# fancontrollermegashield.net
KiCad netlist of a schematic drawn in EAGLE
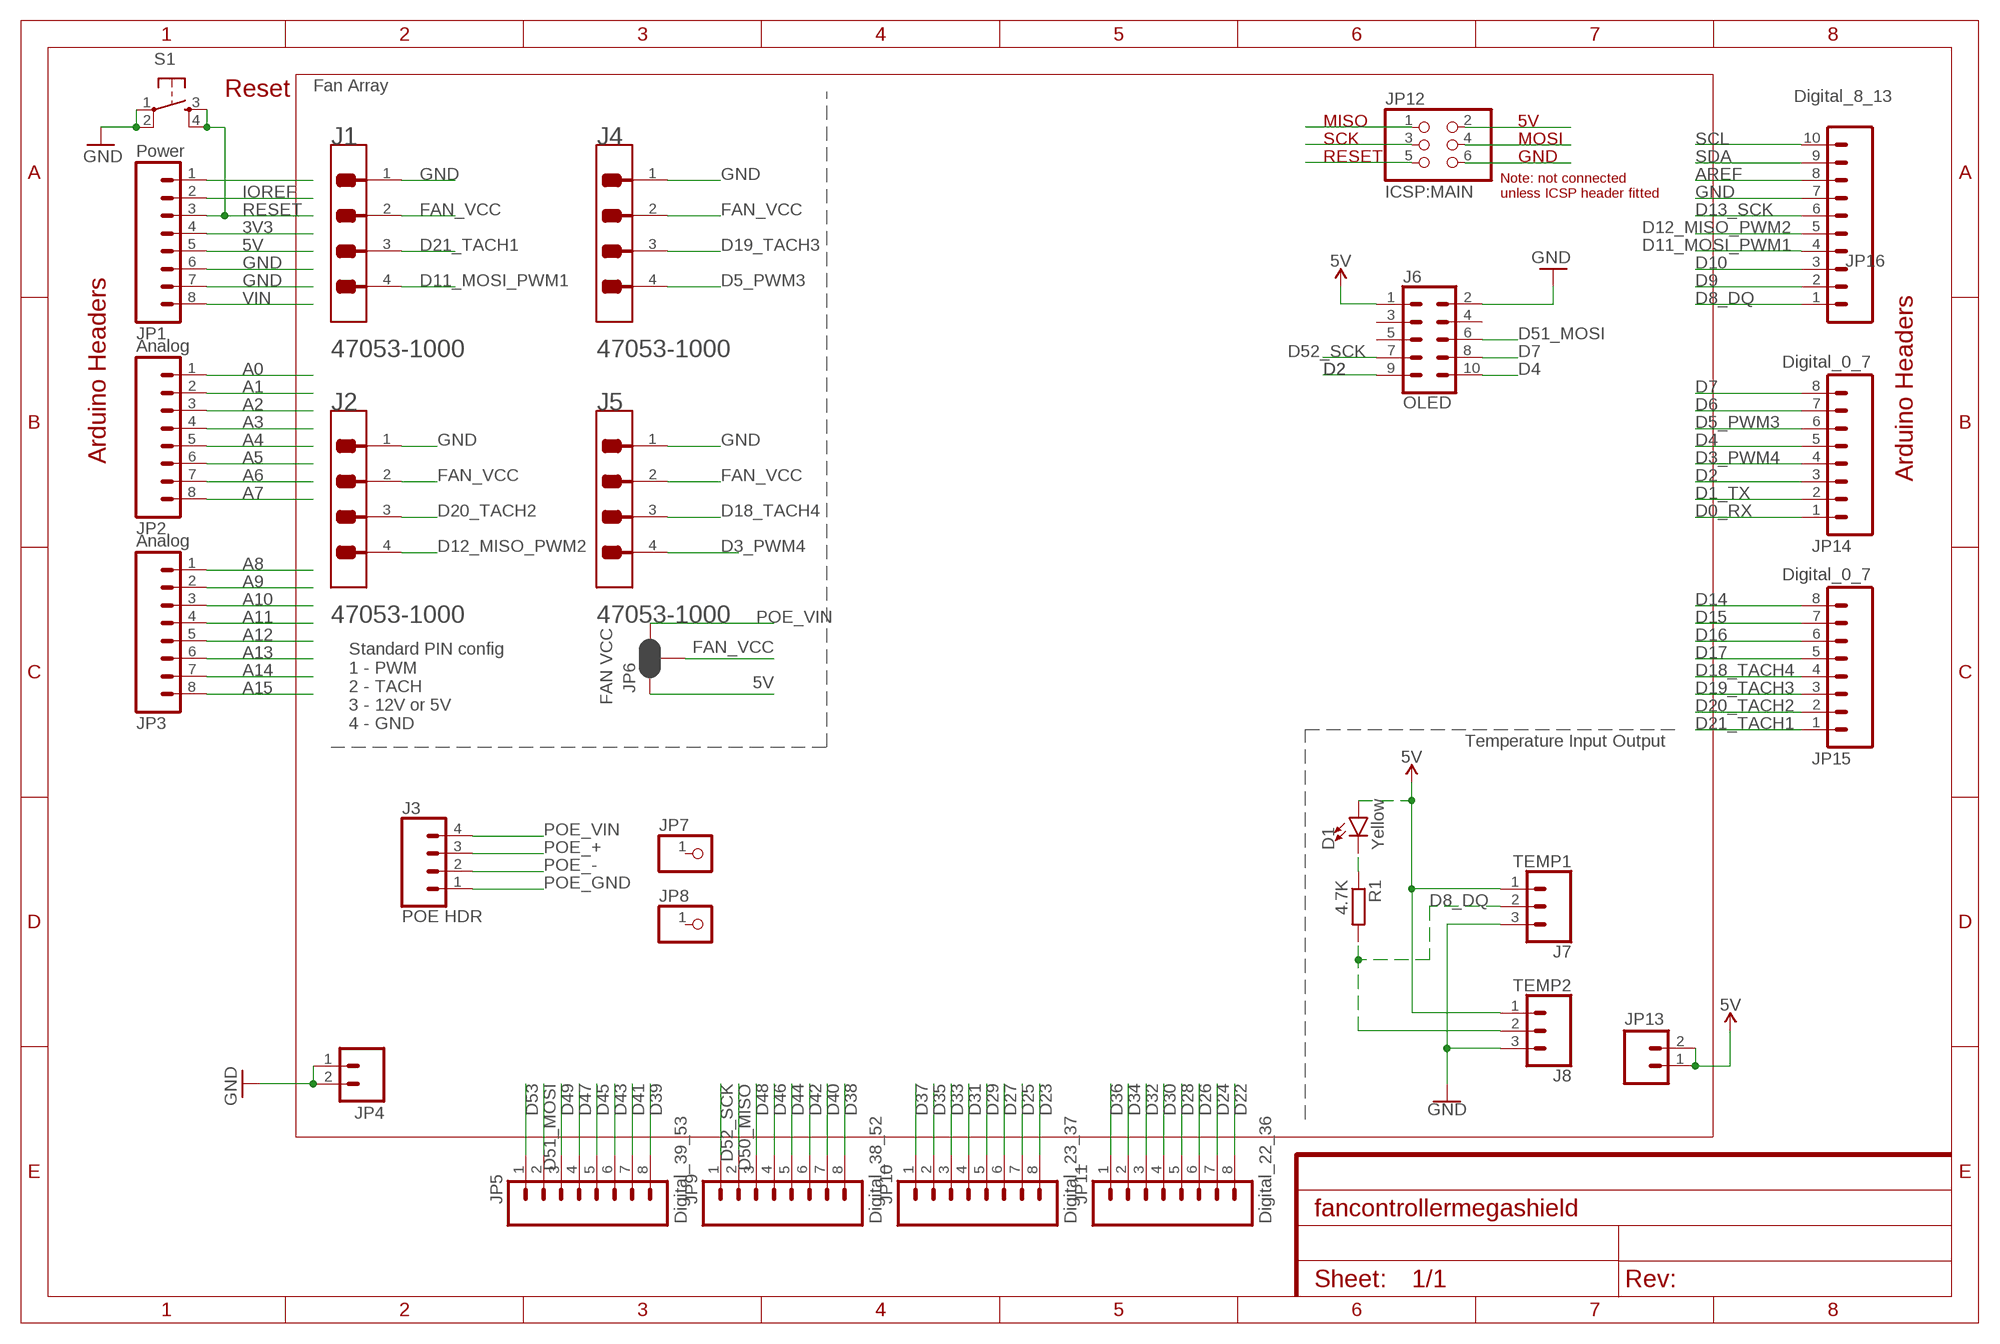
[diagram p0: schematic, sheet 1]

(export (version "E")
  (design (tool "Eeschema 10.0.6"))
  (components
    (comp (ref "D1")
      (value "Yellow")
      (footprint "eagle-import:LED-0603")
      (libsource (lib "eagle-import") (part "LED-YELLOW0603"))
    )
    (comp (ref "J1")
      (value "FAN1")
      (footprint "eagle-import:MOLEX_47053-1000_0")
      (fields
        (field (name "DIGIKEY_PART_NUMBER") "WM4330-ND")
        (field (name "MF") "Molex")
        (field (name "MOUSER_PART_NUMBER") "538-47053-1000")
      )
      (libsource (lib "eagle-import") (part "MOLEX_47053-1000MOLEX_47053-1000_0_0"))
    )
    (comp (ref "J2")
      (value "MOLEX_47053-1000MOLEX_47053-1000_0_0")
      (footprint "eagle-import:MOLEX_47053-1000_0")
      (fields
        (field (name "DIGIKEY_PART_NUMBER") "WM4330-ND")
        (field (name "MF") "Molex")
        (field (name "MOUSER_PART_NUMBER") "538-47053-1000")
      )
      (libsource (lib "eagle-import") (part "MOLEX_47053-1000MOLEX_47053-1000_0_0"))
    )
    (comp (ref "J3")
      (value "POE HDR")
      (footprint "eagle-import:1X04")
      (libsource (lib "eagle-import") (part "CONN_04"))
    )
    (comp (ref "J4")
      (value "MOLEX_47053-1000MOLEX_47053-1000_0_0")
      (footprint "eagle-import:MOLEX_47053-1000_0")
      (fields
        (field (name "DIGIKEY_PART_NUMBER") "WM4330-ND")
        (field (name "MF") "Molex")
        (field (name "MOUSER_PART_NUMBER") "538-47053-1000")
      )
      (libsource (lib "eagle-import") (part "MOLEX_47053-1000MOLEX_47053-1000_0_0"))
    )
    (comp (ref "J5")
      (value "MOLEX_47053-1000MOLEX_47053-1000_0_0")
      (footprint "eagle-import:MOLEX_47053-1000_0")
      (fields
        (field (name "DIGIKEY_PART_NUMBER") "WM4330-ND")
        (field (name "MF") "Molex")
        (field (name "MOUSER_PART_NUMBER") "538-47053-1000")
      )
      (libsource (lib "eagle-import") (part "MOLEX_47053-1000MOLEX_47053-1000_0_0"))
    )
    (comp (ref "J6")
      (value "OLED")
      (footprint "eagle-import:2X5-SHROUDED")
      (libsource (lib "eagle-import") (part "CONN_05X2SHD"))
    )
    (comp (ref "J7")
      (value "TEMP1")
      (footprint "eagle-import:MOLEX-1X3")
      (libsource (lib "eagle-import") (part "CONN_03POLAR"))
    )
    (comp (ref "J8")
      (value "TEMP2")
      (footprint "eagle-import:MOLEX-1X3")
      (libsource (lib "eagle-import") (part "CONN_03POLAR"))
    )
    (comp (ref "JP1")
      (value "Power")
      (footprint "eagle-import:1X08")
      (libsource (lib "eagle-import") (part "freetronics-master-v1_M08"))
    )
    (comp (ref "JP2")
      (value "Analog")
      (footprint "eagle-import:1X08")
      (libsource (lib "eagle-import") (part "freetronics-master-v1_M08"))
    )
    (comp (ref "JP3")
      (value "Analog")
      (footprint "eagle-import:1X08")
      (libsource (lib "eagle-import") (part "freetronics-master-v1_M08"))
    )
    (comp (ref "JP4")
      (value "M02PTH")
      (footprint "eagle-import:1X02")
      (libsource (lib "eagle-import") (part "M02PTH"))
    )
    (comp (ref "JP5")
      (value "Digital_39_53")
      (footprint "eagle-import:1X08")
      (libsource (lib "eagle-import") (part "M08"))
    )
    (comp (ref "JP6")
      (value "FAN VCC")
      (footprint "eagle-import:SMT-JUMPER_3_2-NC_PASTE_SILK")
      (libsource (lib "eagle-import") (part "JUMPER-SMT_3_2-NC_PASTE_SILK"))
    )
    (comp (ref "JP7")
      (value "PINHD-1X1")
      (footprint "eagle-import:1X01")
      (libsource (lib "eagle-import") (part "PINHD-1X1"))
    )
    (comp (ref "JP8")
      (value "PINHD-1X1")
      (footprint "eagle-import:1X01")
      (libsource (lib "eagle-import") (part "PINHD-1X1"))
    )
    (comp (ref "JP9")
      (value "Digital_38_52")
      (footprint "eagle-import:1X08")
      (libsource (lib "eagle-import") (part "M08"))
    )
    (comp (ref "JP10")
      (value "Digital_23_37")
      (footprint "eagle-import:1X08")
      (libsource (lib "eagle-import") (part "M08"))
    )
    (comp (ref "JP11")
      (value "Digital_22_36")
      (footprint "eagle-import:1X08")
      (libsource (lib "eagle-import") (part "M08"))
    )
    (comp (ref "JP12")
      (value "ICSP:MAIN")
      (footprint "eagle-import:2X03")
      (libsource (lib "eagle-import") (part "PINHD-2X3"))
    )
    (comp (ref "JP13")
      (value "M02PTH")
      (footprint "eagle-import:1X02")
      (libsource (lib "eagle-import") (part "M02PTH"))
    )
    (comp (ref "JP14")
      (value "Digital_0_7")
      (footprint "eagle-import:1X08")
      (libsource (lib "eagle-import") (part "M08"))
    )
    (comp (ref "JP15")
      (value "Digital_0_7")
      (footprint "eagle-import:1X08")
      (libsource (lib "eagle-import") (part "M08"))
    )
    (comp (ref "JP16")
      (value "Digital_8_13")
      (footprint "eagle-import:1X10")
      (libsource (lib "eagle-import") (part "M100.1"))
    )
    (comp (ref "R1")
      (value "4.7K")
      (footprint "eagle-import:R0603")
      (libsource (lib "eagle-import") (part "R-EU_R0603"))
    )
    (comp (ref "S1")
      (value "TAC_SWITCHPTH")
      (footprint "eagle-import:TACTILE-PTH")
      (libsource (lib "eagle-import") (part "TAC_SWITCHPTH"))
    )
  )
  (nets
    (net (code "1") (name "/3V3") (class "Default")
      (node (ref "JP1") (pin "4") (pinfunction "4_4") (pintype "passive"))
    )
    (net (code "2") (name "/A0") (class "Default")
      (node (ref "JP2") (pin "1") (pinfunction "1_1") (pintype "passive"))
    )
    (net (code "3") (name "/A1") (class "Default")
      (node (ref "JP2") (pin "2") (pinfunction "2_2") (pintype "passive"))
    )
    (net (code "4") (name "/A2") (class "Default")
      (node (ref "JP2") (pin "3") (pinfunction "3_3") (pintype "passive"))
    )
    (net (code "5") (name "/A3") (class "Default")
      (node (ref "JP2") (pin "4") (pinfunction "4_4") (pintype "passive"))
    )
    (net (code "6") (name "/A4") (class "Default")
      (node (ref "JP2") (pin "5") (pinfunction "5_5") (pintype "passive"))
    )
    (net (code "7") (name "/A5") (class "Default")
      (node (ref "JP2") (pin "6") (pinfunction "6_6") (pintype "passive"))
    )
    (net (code "8") (name "/A6") (class "Default")
      (node (ref "JP2") (pin "7") (pinfunction "7_7") (pintype "passive"))
    )
    (net (code "9") (name "/A7") (class "Default")
      (node (ref "JP2") (pin "8") (pinfunction "8_8") (pintype "passive"))
    )
    (net (code "10") (name "/A8") (class "Default")
      (node (ref "JP3") (pin "1") (pinfunction "1_1") (pintype "passive"))
    )
    (net (code "11") (name "/A9") (class "Default")
      (node (ref "JP3") (pin "2") (pinfunction "2_2") (pintype "passive"))
    )
    (net (code "12") (name "/A10") (class "Default")
      (node (ref "JP3") (pin "3") (pinfunction "3_3") (pintype "passive"))
    )
    (net (code "13") (name "/A11") (class "Default")
      (node (ref "JP3") (pin "4") (pinfunction "4_4") (pintype "passive"))
    )
    (net (code "14") (name "/A12") (class "Default")
      (node (ref "JP3") (pin "5") (pinfunction "5_5") (pintype "passive"))
    )
    (net (code "15") (name "/A13") (class "Default")
      (node (ref "JP3") (pin "6") (pinfunction "6_6") (pintype "passive"))
    )
    (net (code "16") (name "/A14") (class "Default")
      (node (ref "JP3") (pin "7") (pinfunction "7_7") (pintype "passive"))
    )
    (net (code "17") (name "/A15") (class "Default")
      (node (ref "JP3") (pin "8") (pinfunction "8_8") (pintype "passive"))
    )
    (net (code "18") (name "/AREF") (class "Default")
      (node (ref "JP16") (pin "8") (pinfunction "8_8") (pintype "passive"))
    )
    (net (code "19") (name "/D0_RX") (class "Default")
      (node (ref "JP14") (pin "1") (pinfunction "1_1") (pintype "passive"))
    )
    (net (code "20") (name "/D1_TX") (class "Default")
      (node (ref "JP14") (pin "2") (pinfunction "2_2") (pintype "passive"))
    )
    (net (code "21") (name "/D2") (class "Default")
      (node (ref "J6") (pin "9") (pinfunction "9_9") (pintype "passive"))
      (node (ref "JP14") (pin "3") (pinfunction "3_3") (pintype "passive"))
    )
    (net (code "22") (name "/D3_PWM4") (class "Default")
      (node (ref "J5") (pin "4") (pinfunction "4_4") (pintype "bidirectional"))
      (node (ref "JP14") (pin "4") (pinfunction "4_4") (pintype "passive"))
    )
    (net (code "23") (name "/D4") (class "Default")
      (node (ref "J6") (pin "10") (pinfunction "10_10") (pintype "passive"))
      (node (ref "JP14") (pin "5") (pinfunction "5_5") (pintype "passive"))
    )
    (net (code "24") (name "/D5_PWM3") (class "Default")
      (node (ref "J4") (pin "4") (pinfunction "4_4") (pintype "bidirectional"))
      (node (ref "JP14") (pin "6") (pinfunction "6_6") (pintype "passive"))
    )
    (net (code "25") (name "/D6") (class "Default")
      (node (ref "JP14") (pin "7") (pinfunction "7_7") (pintype "passive"))
    )
    (net (code "26") (name "/D7") (class "Default")
      (node (ref "J6") (pin "8") (pinfunction "8_8") (pintype "passive"))
      (node (ref "JP14") (pin "8") (pinfunction "8_8") (pintype "passive"))
    )
    (net (code "27") (name "/D8_DQ") (class "Default")
      (node (ref "J7") (pin "2") (pinfunction "2_2") (pintype "passive"))
      (node (ref "J8") (pin "2") (pinfunction "2_2") (pintype "passive"))
      (node (ref "JP16") (pin "1") (pinfunction "1_1") (pintype "passive"))
      (node (ref "R1") (pin "2") (pinfunction "2_2") (pintype "passive"))
    )
    (net (code "28") (name "/D9") (class "Default")
      (node (ref "JP16") (pin "2") (pinfunction "2_2") (pintype "passive"))
    )
    (net (code "29") (name "/D10") (class "Default")
      (node (ref "JP16") (pin "3") (pinfunction "3_3") (pintype "passive"))
    )
    (net (code "30") (name "/D11_MOSI_PWM1") (class "Default")
      (node (ref "J1") (pin "4") (pinfunction "4_4") (pintype "bidirectional"))
      (node (ref "JP16") (pin "4") (pinfunction "4_4") (pintype "passive"))
    )
    (net (code "31") (name "/D12_MISO_PWM2") (class "Default")
      (node (ref "J2") (pin "4") (pinfunction "4_4") (pintype "bidirectional"))
      (node (ref "JP16") (pin "5") (pinfunction "5_5") (pintype "passive"))
    )
    (net (code "32") (name "/D13_SCK") (class "Default")
      (node (ref "JP16") (pin "6") (pinfunction "6_6") (pintype "passive"))
    )
    (net (code "33") (name "/D14") (class "Default")
      (node (ref "JP15") (pin "8") (pinfunction "8_8") (pintype "passive"))
    )
    (net (code "34") (name "/D15") (class "Default")
      (node (ref "JP15") (pin "7") (pinfunction "7_7") (pintype "passive"))
    )
    (net (code "35") (name "/D16") (class "Default")
      (node (ref "JP15") (pin "6") (pinfunction "6_6") (pintype "passive"))
    )
    (net (code "36") (name "/D17") (class "Default")
      (node (ref "JP15") (pin "5") (pinfunction "5_5") (pintype "passive"))
    )
    (net (code "37") (name "/D18_TACH4") (class "Default")
      (node (ref "J5") (pin "3") (pinfunction "3_3") (pintype "bidirectional"))
      (node (ref "JP15") (pin "4") (pinfunction "4_4") (pintype "passive"))
    )
    (net (code "38") (name "/D19_TACH3") (class "Default")
      (node (ref "J4") (pin "3") (pinfunction "3_3") (pintype "bidirectional"))
      (node (ref "JP15") (pin "3") (pinfunction "3_3") (pintype "passive"))
    )
    (net (code "39") (name "/D20_TACH2") (class "Default")
      (node (ref "J2") (pin "3") (pinfunction "3_3") (pintype "bidirectional"))
      (node (ref "JP15") (pin "2") (pinfunction "2_2") (pintype "passive"))
    )
    (net (code "40") (name "/D21_TACH1") (class "Default")
      (node (ref "J1") (pin "3") (pinfunction "3_3") (pintype "bidirectional"))
      (node (ref "JP15") (pin "1") (pinfunction "1_1") (pintype "passive"))
    )
    (net (code "41") (name "/D22") (class "Default")
      (node (ref "JP11") (pin "8") (pinfunction "8_8") (pintype "passive"))
    )
    (net (code "42") (name "/D23") (class "Default")
      (node (ref "JP10") (pin "8") (pinfunction "8_8") (pintype "passive"))
    )
    (net (code "43") (name "/D24") (class "Default")
      (node (ref "JP11") (pin "7") (pinfunction "7_7") (pintype "passive"))
    )
    (net (code "44") (name "/D25") (class "Default")
      (node (ref "JP10") (pin "7") (pinfunction "7_7") (pintype "passive"))
    )
    (net (code "45") (name "/D26") (class "Default")
      (node (ref "JP11") (pin "6") (pinfunction "6_6") (pintype "passive"))
    )
    (net (code "46") (name "/D27") (class "Default")
      (node (ref "JP10") (pin "6") (pinfunction "6_6") (pintype "passive"))
    )
    (net (code "47") (name "/D28") (class "Default")
      (node (ref "JP11") (pin "5") (pinfunction "5_5") (pintype "passive"))
    )
    (net (code "48") (name "/D29") (class "Default")
      (node (ref "JP10") (pin "5") (pinfunction "5_5") (pintype "passive"))
    )
    (net (code "49") (name "/D30") (class "Default")
      (node (ref "JP11") (pin "4") (pinfunction "4_4") (pintype "passive"))
    )
    (net (code "50") (name "/D31") (class "Default")
      (node (ref "JP10") (pin "4") (pinfunction "4_4") (pintype "passive"))
    )
    (net (code "51") (name "/D32") (class "Default")
      (node (ref "JP11") (pin "3") (pinfunction "3_3") (pintype "passive"))
    )
    (net (code "52") (name "/D33") (class "Default")
      (node (ref "JP10") (pin "3") (pinfunction "3_3") (pintype "passive"))
    )
    (net (code "53") (name "/D34") (class "Default")
      (node (ref "JP11") (pin "2") (pinfunction "2_2") (pintype "passive"))
    )
    (net (code "54") (name "/D35") (class "Default")
      (node (ref "JP10") (pin "2") (pinfunction "2_2") (pintype "passive"))
    )
    (net (code "55") (name "/D36") (class "Default")
      (node (ref "JP11") (pin "1") (pinfunction "1_1") (pintype "passive"))
    )
    (net (code "56") (name "/D37") (class "Default")
      (node (ref "JP10") (pin "1") (pinfunction "1_1") (pintype "passive"))
    )
    (net (code "57") (name "/D38") (class "Default")
      (node (ref "JP9") (pin "8") (pinfunction "8_8") (pintype "passive"))
    )
    (net (code "58") (name "/D39") (class "Default")
      (node (ref "JP5") (pin "8") (pinfunction "8_8") (pintype "passive"))
    )
    (net (code "59") (name "/D40") (class "Default")
      (node (ref "JP9") (pin "7") (pinfunction "7_7") (pintype "passive"))
    )
    (net (code "60") (name "/D41") (class "Default")
      (node (ref "JP5") (pin "7") (pinfunction "7_7") (pintype "passive"))
    )
    (net (code "61") (name "/D42") (class "Default")
      (node (ref "JP9") (pin "6") (pinfunction "6_6") (pintype "passive"))
    )
    (net (code "62") (name "/D43") (class "Default")
      (node (ref "JP5") (pin "6") (pinfunction "6_6") (pintype "passive"))
    )
    (net (code "63") (name "/D44") (class "Default")
      (node (ref "JP9") (pin "5") (pinfunction "5_5") (pintype "passive"))
    )
    (net (code "64") (name "/D45") (class "Default")
      (node (ref "JP5") (pin "5") (pinfunction "5_5") (pintype "passive"))
    )
    (net (code "65") (name "/D46") (class "Default")
      (node (ref "JP9") (pin "4") (pinfunction "4_4") (pintype "passive"))
    )
    (net (code "66") (name "/D47") (class "Default")
      (node (ref "JP5") (pin "4") (pinfunction "4_4") (pintype "passive"))
    )
    (net (code "67") (name "/D48") (class "Default")
      (node (ref "JP9") (pin "3") (pinfunction "3_3") (pintype "passive"))
    )
    (net (code "68") (name "/D49") (class "Default")
      (node (ref "JP5") (pin "3") (pinfunction "3_3") (pintype "passive"))
    )
    (net (code "69") (name "/D50_MISO") (class "Default")
      (node (ref "JP9") (pin "2") (pinfunction "2_2") (pintype "passive"))
    )
    (net (code "70") (name "/D51_MOSI") (class "Default")
      (node (ref "J6") (pin "6") (pinfunction "6_6") (pintype "passive"))
      (node (ref "JP5") (pin "2") (pinfunction "2_2") (pintype "passive"))
    )
    (net (code "71") (name "/D52_SCK") (class "Default")
      (node (ref "J6") (pin "7") (pinfunction "7_7") (pintype "passive"))
      (node (ref "JP9") (pin "1") (pinfunction "1_1") (pintype "passive"))
    )
    (net (code "72") (name "/D53") (class "Default")
      (node (ref "JP5") (pin "1") (pinfunction "1_1") (pintype "passive"))
    )
    (net (code "73") (name "/FAN_VCC") (class "Default")
      (node (ref "J1") (pin "2") (pinfunction "2_2") (pintype "bidirectional"))
      (node (ref "J2") (pin "2") (pinfunction "2_2") (pintype "bidirectional"))
      (node (ref "J4") (pin "2") (pinfunction "2_2") (pintype "bidirectional"))
      (node (ref "J5") (pin "2") (pinfunction "2_2") (pintype "bidirectional"))
      (node (ref "JP6") (pin "2") (pinfunction "2_2") (pintype "passive"))
    )
    (net (code "74") (name "/IOREF") (class "Default")
      (node (ref "JP1") (pin "2") (pinfunction "2_2") (pintype "passive"))
    )
    (net (code "75") (name "/POE_+") (class "Default")
      (node (ref "J3") (pin "3") (pinfunction "3_3") (pintype "passive"))
    )
    (net (code "76") (name "/POE_-") (class "Default")
      (node (ref "J3") (pin "2") (pinfunction "2_2") (pintype "passive"))
    )
    (net (code "77") (name "/POE_GND") (class "Default")
      (node (ref "J3") (pin "1") (pinfunction "1_1") (pintype "passive"))
    )
    (net (code "78") (name "/POE_VIN") (class "Default")
      (node (ref "J3") (pin "4") (pinfunction "4_4") (pintype "passive"))
      (node (ref "JP6") (pin "3") (pinfunction "3_3") (pintype "passive"))
    )
    (net (code "79") (name "/RESET") (class "Default")
      (node (ref "JP1") (pin "3") (pinfunction "3_3") (pintype "passive"))
      (node (ref "S1") (pin "3") (pinfunction "3_3") (pintype "passive"))
      (node (ref "S1") (pin "4") (pinfunction "4_4") (pintype "passive"))
    )
    (net (code "80") (name "/SCL") (class "Default")
      (node (ref "JP16") (pin "10") (pinfunction "10_10") (pintype "passive"))
    )
    (net (code "81") (name "/SDA") (class "Default")
      (node (ref "JP16") (pin "9") (pinfunction "9_9") (pintype "passive"))
    )
    (net (code "82") (name "/VIN") (class "Default")
      (node (ref "JP1") (pin "8") (pinfunction "8_8") (pintype "passive"))
    )
    (net (code "83") (name "5V") (class "Default")
      (node (ref "D1") (pin "A") (pinfunction "A_A") (pintype "passive"))
      (node (ref "J6") (pin "1") (pinfunction "1_1") (pintype "passive"))
      (node (ref "J7") (pin "1") (pinfunction "1_1") (pintype "passive"))
      (node (ref "J8") (pin "1") (pinfunction "1_1") (pintype "passive"))
      (node (ref "JP1") (pin "5") (pinfunction "5_5") (pintype "passive"))
      (node (ref "JP13") (pin "1") (pinfunction "1_1") (pintype "passive"))
      (node (ref "JP13") (pin "2") (pinfunction "2_2") (pintype "passive"))
      (node (ref "JP6") (pin "1") (pinfunction "1_1") (pintype "passive"))
    )
    (net (code "84") (name "GND") (class "Default")
      (node (ref "J1") (pin "1") (pinfunction "1_1") (pintype "bidirectional"))
      (node (ref "J2") (pin "1") (pinfunction "1_1") (pintype "bidirectional"))
      (node (ref "J4") (pin "1") (pinfunction "1_1") (pintype "bidirectional"))
      (node (ref "J5") (pin "1") (pinfunction "1_1") (pintype "bidirectional"))
      (node (ref "J6") (pin "2") (pinfunction "2_2") (pintype "passive"))
      (node (ref "J7") (pin "3") (pinfunction "3_3") (pintype "passive"))
      (node (ref "J8") (pin "3") (pinfunction "3_3") (pintype "passive"))
      (node (ref "JP1") (pin "6") (pinfunction "6_6") (pintype "passive"))
      (node (ref "JP1") (pin "7") (pinfunction "7_7") (pintype "passive"))
      (node (ref "JP16") (pin "7") (pinfunction "7_7") (pintype "passive"))
      (node (ref "JP4") (pin "1") (pinfunction "1_1") (pintype "passive"))
      (node (ref "JP4") (pin "2") (pinfunction "2_2") (pintype "passive"))
      (node (ref "S1") (pin "1") (pinfunction "1_1") (pintype "passive"))
      (node (ref "S1") (pin "2") (pinfunction "2_2") (pintype "passive"))
    )
    (net (code "85") (name "Net-(D1-PadC)") (class "Default")
      (node (ref "D1") (pin "C") (pinfunction "C_C") (pintype "passive"))
      (node (ref "R1") (pin "1") (pinfunction "1_1") (pintype "passive"))
    )
    (net (code "86") (name "unconnected-(J6-Pad3)") (class "Default")
      (node (ref "J6") (pin "3") (pinfunction "3_3") (pintype "passive"))
    )
    (net (code "87") (name "unconnected-(J6-Pad4)") (class "Default")
      (node (ref "J6") (pin "4") (pinfunction "4_4") (pintype "passive"))
    )
    (net (code "88") (name "unconnected-(J6-Pad5)") (class "Default")
      (node (ref "J6") (pin "5") (pinfunction "5_5") (pintype "passive"))
    )
    (net (code "89") (name "unconnected-(JP1-Pad1)") (class "Default")
      (node (ref "JP1") (pin "1") (pinfunction "1_1") (pintype "passive"))
    )
    (net (code "90") (name "unconnected-(JP7-Pad1)") (class "Default")
      (node (ref "JP7") (pin "1") (pinfunction "1_1") (pintype "passive"))
    )
    (net (code "91") (name "unconnected-(JP8-Pad1)") (class "Default")
      (node (ref "JP8") (pin "1") (pinfunction "1_1") (pintype "passive"))
    )
    (net (code "92") (name "unconnected-(JP12-Pad1)") (class "Default")
      (node (ref "JP12") (pin "1") (pinfunction "1_1") (pintype "passive"))
    )
    (net (code "93") (name "unconnected-(JP12-Pad2)") (class "Default")
      (node (ref "JP12") (pin "2") (pinfunction "2_2") (pintype "passive"))
    )
    (net (code "94") (name "unconnected-(JP12-Pad3)") (class "Default")
      (node (ref "JP12") (pin "3") (pinfunction "3_3") (pintype "passive"))
    )
    (net (code "95") (name "unconnected-(JP12-Pad4)") (class "Default")
      (node (ref "JP12") (pin "4") (pinfunction "4_4") (pintype "passive"))
    )
    (net (code "96") (name "unconnected-(JP12-Pad5)") (class "Default")
      (node (ref "JP12") (pin "5") (pinfunction "5_5") (pintype "passive"))
    )
    (net (code "97") (name "unconnected-(JP12-Pad6)") (class "Default")
      (node (ref "JP12") (pin "6") (pinfunction "6_6") (pintype "passive"))
    )
  )
)
